# LED_TwoBars.net
KiCad netlist of a schematic drawn in Altium Designer
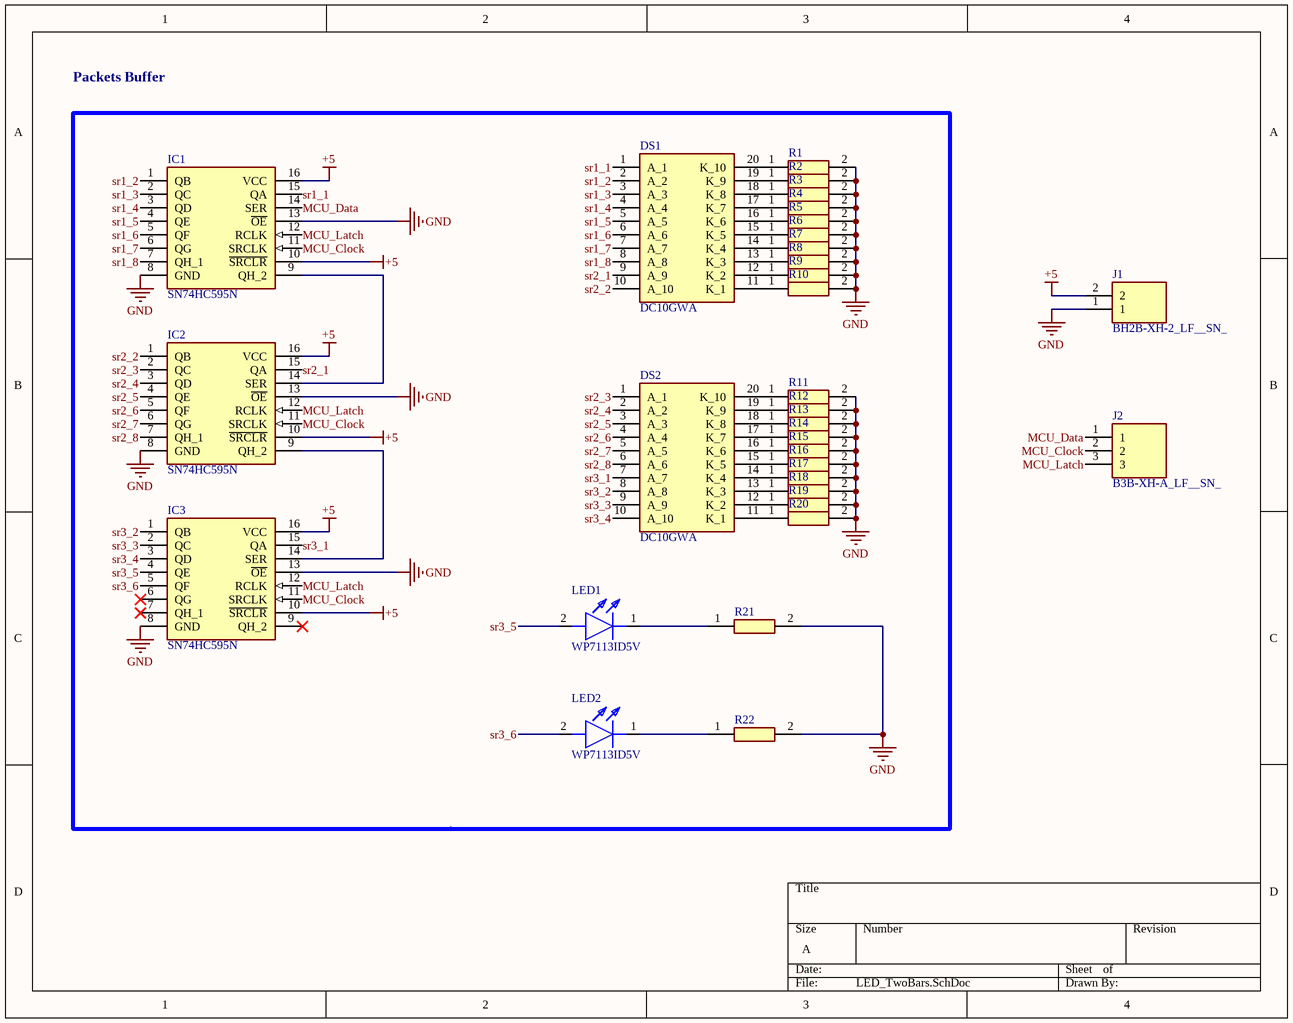
[diagram p0: LED_TwoBars.SchDoc]

(export (version "E")
  (design (tool "Eeschema 10.0.6"))
  (components
    (comp (ref "DS1")
      (value "DC10GWA")
      (footprint "LED_Buffer:DIPS750W75P254L2540H825Q20N")
      (description "Display")
      (fields (field (name "MOUSER PART NUMBER") "604-DC10GWA"))
      (libsource (lib "*") (part "DC10GWA"))
    )
    (comp (ref "DS2")
      (value "DC10GWA")
      (footprint "LED_Buffer:DIPS750W75P254L2540H825Q20N")
      (description "Display")
      (fields (field (name "MOUSER PART NUMBER") "604-DC10GWA"))
      (libsource (lib "*") (part "DC10GWA"))
    )
    (comp (ref "IC1")
      (value "SN74HC595N")
      (footprint "LED_Buffer:DIP794W53P254L1930H508Q16N")
      (description "Integrated Circuit")
      (fields (field (name "MOUSER PART NUMBER") "595-SN74HC595N"))
      (libsource (lib "*") (part "SN74HC595N"))
    )
    (comp (ref "IC2")
      (value "SN74HC595N")
      (footprint "LED_Buffer:DIP794W53P254L1930H508Q16N")
      (description "Integrated Circuit")
      (fields (field (name "MOUSER PART NUMBER") "595-SN74HC595N"))
      (libsource (lib "*") (part "SN74HC595N"))
    )
    (comp (ref "IC3")
      (value "SN74HC595N")
      (footprint "LED_Buffer:DIP794W53P254L1930H508Q16N")
      (description "Integrated Circuit")
      (fields (field (name "MOUSER PART NUMBER") "595-SN74HC595N"))
      (libsource (lib "*") (part "SN74HC595N"))
    )
    (comp (ref "J1")
      (value "BH2B-XH-2_LF__SN_")
      (footprint "LED_Buffer:BH2BXH2LFSN")
      (description "Connector")
      (fields (field (name "MANUFACTURER_PART_NUMBER") "BH2B-XH-2(LF)(SN)"))
      (libsource (lib "LED_Buffer") (part "BH2B-XH-2_LF__SN_"))
    )
    (comp (ref "J2")
      (value "B3B-XH-A_LF__SN_")
      (footprint "LED_Buffer:B3BXHALFSN")
      (description "Connector")
      (fields
        (field (name "MANUFACTURER_PART_NUMBER") "B3B-XH-A(LF)(SN)")
        (field (name "MOUSER PART NUMBER") "306-B3BXHALFSNP")
      )
      (libsource (lib "*") (part "B3B-XH-A_LF__SN_"))
    )
    (comp (ref "LED1")
      (value "WP7113ID5V")
      (footprint "LED_TwoBars:WP7113ID5V")
      (description "LED")
      (fields (field (name "MOUSER PART NUMBER") "604-WP7113ID5V"))
      (libsource (lib "*") (part "WP7113ID5V"))
    )
    (comp (ref "LED2")
      (value "WP7113ID5V")
      (footprint "LED_TwoBars:WP7113ID5V")
      (description "LED")
      (fields (field (name "MOUSER PART NUMBER") "604-WP7113ID5V"))
      (libsource (lib "*") (part "WP7113ID5V"))
    )
    (comp (ref "R1")
      (value "330")
      (footprint "LED_Buffer:RESC3126X65N")
      (description "Resistor")
      (fields (field (name "MANUFACTURER_PART_NUMBER") "RC1210FR-07330RL"))
      (libsource (lib "*") (part "RC1210FR-07330RL"))
    )
    (comp (ref "R2")
      (value "RC1210FR-07330RL")
      (footprint "LED_Buffer:RESC3126X65N")
      (description "Resistor")
      (libsource (lib "*") (part "RC1210FR-07330RL"))
    )
    (comp (ref "R3")
      (value "330")
      (footprint "LED_Buffer:RESC3126X65N")
      (description "Resistor")
      (fields (field (name "MANUFACTURER_PART_NUMBER") "RC1210FR-07330RL"))
      (libsource (lib "*") (part "RC1210FR-07330RL"))
    )
    (comp (ref "R4")
      (value "RC1210FR-07330RL")
      (footprint "LED_Buffer:RESC3126X65N")
      (description "Resistor")
      (libsource (lib "*") (part "RC1210FR-07330RL"))
    )
    (comp (ref "R5")
      (value "330")
      (footprint "LED_Buffer:RESC3126X65N")
      (description "Resistor")
      (fields (field (name "MANUFACTURER_PART_NUMBER") "RC1210FR-07330RL"))
      (libsource (lib "*") (part "RC1210FR-07330RL"))
    )
    (comp (ref "R6")
      (value "RC1210FR-07330RL")
      (footprint "LED_Buffer:RESC3126X65N")
      (description "Resistor")
      (libsource (lib "*") (part "RC1210FR-07330RL"))
    )
    (comp (ref "R7")
      (value "330")
      (footprint "LED_Buffer:RESC3126X65N")
      (description "Resistor")
      (fields (field (name "MANUFACTURER_PART_NUMBER") "RC1210FR-07330RL"))
      (libsource (lib "*") (part "RC1210FR-07330RL"))
    )
    (comp (ref "R8")
      (value "RC1210FR-07330RL")
      (footprint "LED_Buffer:RESC3126X65N")
      (description "Resistor")
      (libsource (lib "*") (part "RC1210FR-07330RL"))
    )
    (comp (ref "R9")
      (value "330")
      (footprint "LED_Buffer:RESC3126X65N")
      (description "Resistor")
      (fields (field (name "MANUFACTURER_PART_NUMBER") "RC1210FR-07330RL"))
      (libsource (lib "*") (part "RC1210FR-07330RL"))
    )
    (comp (ref "R10")
      (value "330")
      (footprint "LED_Buffer:RESC3126X65N")
      (description "Resistor")
      (fields (field (name "MANUFACTURER_PART_NUMBER") "RC1210FR-07330RL"))
      (libsource (lib "*") (part "RC1210FR-07330RL"))
    )
    (comp (ref "R11")
      (value "330")
      (footprint "LED_Buffer:RESC3126X65N")
      (description "Resistor")
      (fields (field (name "MANUFACTURER_PART_NUMBER") "RC1210FR-07330RL"))
      (libsource (lib "*") (part "RC1210FR-07330RL"))
    )
    (comp (ref "R12")
      (value "330")
      (footprint "LED_Buffer:RESC3126X65N")
      (description "Resistor")
      (fields (field (name "MANUFACTURER_PART_NUMBER") "RC1210FR-07330RL"))
      (libsource (lib "*") (part "RC1210FR-07330RL"))
    )
    (comp (ref "R13")
      (value "330")
      (footprint "LED_Buffer:RESC3126X65N")
      (description "Resistor")
      (fields (field (name "MANUFACTURER_PART_NUMBER") "RC1210FR-07330RL"))
      (libsource (lib "*") (part "RC1210FR-07330RL"))
    )
    (comp (ref "R14")
      (value "330")
      (footprint "LED_Buffer:RESC3126X65N")
      (description "Resistor")
      (fields (field (name "MANUFACTURER_PART_NUMBER") "RC1210FR-07330RL"))
      (libsource (lib "*") (part "RC1210FR-07330RL"))
    )
    (comp (ref "R15")
      (value "330")
      (footprint "LED_Buffer:RESC3126X65N")
      (description "Resistor")
      (fields (field (name "MANUFACTURER_PART_NUMBER") "RC1210FR-07330RL"))
      (libsource (lib "*") (part "RC1210FR-07330RL"))
    )
    (comp (ref "R16")
      (value "330")
      (footprint "LED_Buffer:RESC3126X65N")
      (description "Resistor")
      (fields (field (name "MANUFACTURER_PART_NUMBER") "RC1210FR-07330RL"))
      (libsource (lib "*") (part "RC1210FR-07330RL"))
    )
    (comp (ref "R17")
      (value "330")
      (footprint "LED_Buffer:RESC3126X65N")
      (description "Resistor")
      (fields (field (name "MANUFACTURER_PART_NUMBER") "RC1210FR-07330RL"))
      (libsource (lib "*") (part "RC1210FR-07330RL"))
    )
    (comp (ref "R18")
      (value "330")
      (footprint "LED_Buffer:RESC3126X65N")
      (description "Resistor")
      (fields (field (name "MANUFACTURER_PART_NUMBER") "RC1210FR-07330RL"))
      (libsource (lib "*") (part "RC1210FR-07330RL"))
    )
    (comp (ref "R19")
      (value "RC1210FR-07330RL")
      (footprint "LED_Buffer:RESC3126X65N")
      (description "Resistor")
      (libsource (lib "*") (part "RC1210FR-07330RL"))
    )
    (comp (ref "R20")
      (value "330")
      (footprint "LED_Buffer:RESC3126X65N")
      (description "Resistor")
      (fields (field (name "MANUFACTURER_PART_NUMBER") "RC1210FR-07330RL"))
      (libsource (lib "*") (part "RC1210FR-07330RL"))
    )
    (comp (ref "R21")
      (value "330")
      (footprint "LED_Buffer:RESC3126X65N")
      (description "Resistor")
      (fields (field (name "MANUFACTURER_PART_NUMBER") "RC1210FR-07330RL"))
      (libsource (lib "*") (part "RC1210FR-07330RL"))
    )
    (comp (ref "R22")
      (value "330")
      (footprint "LED_Buffer:RESC3126X65N")
      (description "Resistor")
      (fields (field (name "MANUFACTURER_PART_NUMBER") "RC1210FR-07330RL"))
      (libsource (lib "*") (part "RC1210FR-07330RL"))
    )
  )
  (nets
    (net (code "1") (name "+5") (class "Default")
      (node (ref "IC1") (pin "10") (pinfunction "~{SRCLR}_10") (pintype "passive"))
      (node (ref "IC1") (pin "16") (pinfunction "VCC_16") (pintype "power_in"))
      (node (ref "IC2") (pin "10") (pinfunction "~{SRCLR}_10") (pintype "passive"))
      (node (ref "IC2") (pin "16") (pinfunction "VCC_16") (pintype "power_in"))
      (node (ref "IC3") (pin "10") (pinfunction "~{SRCLR}_10") (pintype "passive"))
      (node (ref "IC3") (pin "16") (pinfunction "VCC_16") (pintype "power_in"))
      (node (ref "J1") (pin "2") (pinfunction "2_2") (pintype "passive"))
    )
    (net (code "2") (name "/MCU_Clock") (class "Default")
      (node (ref "IC1") (pin "11") (pinfunction "SRCLK_11") (pintype "input"))
      (node (ref "IC2") (pin "11") (pinfunction "SRCLK_11") (pintype "input"))
      (node (ref "IC3") (pin "11") (pinfunction "SRCLK_11") (pintype "input"))
      (node (ref "J2") (pin "2") (pinfunction "2_2") (pintype "passive"))
    )
    (net (code "3") (name "/MCU_Data") (class "Default")
      (node (ref "IC1") (pin "14") (pinfunction "SER_14") (pintype "passive"))
      (node (ref "J2") (pin "1") (pinfunction "1_1") (pintype "passive"))
    )
    (net (code "4") (name "/MCU_Latch") (class "Default")
      (node (ref "IC1") (pin "12") (pinfunction "RCLK_12") (pintype "input"))
      (node (ref "IC2") (pin "12") (pinfunction "RCLK_12") (pintype "input"))
      (node (ref "IC3") (pin "12") (pinfunction "RCLK_12") (pintype "input"))
      (node (ref "J2") (pin "3") (pinfunction "3_3") (pintype "passive"))
    )
    (net (code "5") (name "/sr1_1") (class "Default")
      (node (ref "DS1") (pin "1") (pinfunction "A_1_1") (pintype "passive"))
      (node (ref "IC1") (pin "15") (pinfunction "QA_15") (pintype "passive"))
    )
    (net (code "6") (name "/sr1_2") (class "Default")
      (node (ref "DS1") (pin "2") (pinfunction "A_2_2") (pintype "passive"))
      (node (ref "IC1") (pin "1") (pinfunction "QB_1") (pintype "passive"))
    )
    (net (code "7") (name "/sr1_3") (class "Default")
      (node (ref "DS1") (pin "3") (pinfunction "A_3_3") (pintype "passive"))
      (node (ref "IC1") (pin "2") (pinfunction "QC_2") (pintype "passive"))
    )
    (net (code "8") (name "/sr1_4") (class "Default")
      (node (ref "DS1") (pin "4") (pinfunction "A_4_4") (pintype "passive"))
      (node (ref "IC1") (pin "3") (pinfunction "QD_3") (pintype "passive"))
    )
    (net (code "9") (name "/sr1_5") (class "Default")
      (node (ref "DS1") (pin "5") (pinfunction "A_5_5") (pintype "passive"))
      (node (ref "IC1") (pin "4") (pinfunction "QE_4") (pintype "passive"))
    )
    (net (code "10") (name "/sr1_6") (class "Default")
      (node (ref "DS1") (pin "6") (pinfunction "A_6_6") (pintype "passive"))
      (node (ref "IC1") (pin "5") (pinfunction "QF_5") (pintype "passive"))
    )
    (net (code "11") (name "/sr1_7") (class "Default")
      (node (ref "DS1") (pin "7") (pinfunction "A_7_7") (pintype "passive"))
      (node (ref "IC1") (pin "6") (pinfunction "QG_6") (pintype "passive"))
    )
    (net (code "12") (name "/sr1_8") (class "Default")
      (node (ref "DS1") (pin "8") (pinfunction "A_8_8") (pintype "passive"))
      (node (ref "IC1") (pin "7") (pinfunction "QH_1_7") (pintype "passive"))
    )
    (net (code "13") (name "/sr2_1") (class "Default")
      (node (ref "DS1") (pin "9") (pinfunction "A_9_9") (pintype "passive"))
      (node (ref "IC2") (pin "15") (pinfunction "QA_15") (pintype "passive"))
    )
    (net (code "14") (name "/sr2_2") (class "Default")
      (node (ref "DS1") (pin "10") (pinfunction "A_10_10") (pintype "passive"))
      (node (ref "IC2") (pin "1") (pinfunction "QB_1") (pintype "passive"))
    )
    (net (code "15") (name "/sr2_3") (class "Default")
      (node (ref "DS2") (pin "1") (pinfunction "A_1_1") (pintype "passive"))
      (node (ref "IC2") (pin "2") (pinfunction "QC_2") (pintype "passive"))
    )
    (net (code "16") (name "/sr2_4") (class "Default")
      (node (ref "DS2") (pin "2") (pinfunction "A_2_2") (pintype "passive"))
      (node (ref "IC2") (pin "3") (pinfunction "QD_3") (pintype "passive"))
    )
    (net (code "17") (name "/sr2_5") (class "Default")
      (node (ref "DS2") (pin "3") (pinfunction "A_3_3") (pintype "passive"))
      (node (ref "IC2") (pin "4") (pinfunction "QE_4") (pintype "passive"))
    )
    (net (code "18") (name "/sr2_6") (class "Default")
      (node (ref "DS2") (pin "4") (pinfunction "A_4_4") (pintype "passive"))
      (node (ref "IC2") (pin "5") (pinfunction "QF_5") (pintype "passive"))
    )
    (net (code "19") (name "/sr2_7") (class "Default")
      (node (ref "DS2") (pin "5") (pinfunction "A_5_5") (pintype "passive"))
      (node (ref "IC2") (pin "6") (pinfunction "QG_6") (pintype "passive"))
    )
    (net (code "20") (name "/sr2_8") (class "Default")
      (node (ref "DS2") (pin "6") (pinfunction "A_6_6") (pintype "passive"))
      (node (ref "IC2") (pin "7") (pinfunction "QH_1_7") (pintype "passive"))
    )
    (net (code "21") (name "/sr3_1") (class "Default")
      (node (ref "DS2") (pin "7") (pinfunction "A_7_7") (pintype "passive"))
      (node (ref "IC3") (pin "15") (pinfunction "QA_15") (pintype "passive"))
    )
    (net (code "22") (name "/sr3_2") (class "Default")
      (node (ref "DS2") (pin "8") (pinfunction "A_8_8") (pintype "passive"))
      (node (ref "IC3") (pin "1") (pinfunction "QB_1") (pintype "passive"))
    )
    (net (code "23") (name "/sr3_3") (class "Default")
      (node (ref "DS2") (pin "9") (pinfunction "A_9_9") (pintype "passive"))
      (node (ref "IC3") (pin "2") (pinfunction "QC_2") (pintype "passive"))
    )
    (net (code "24") (name "/sr3_4") (class "Default")
      (node (ref "DS2") (pin "10") (pinfunction "A_10_10") (pintype "passive"))
      (node (ref "IC3") (pin "3") (pinfunction "QD_3") (pintype "passive"))
    )
    (net (code "25") (name "/sr3_5") (class "Default")
      (node (ref "IC3") (pin "4") (pinfunction "QE_4") (pintype "passive"))
      (node (ref "LED1") (pin "2") (pinfunction "A_2") (pintype "passive"))
    )
    (net (code "26") (name "/sr3_6") (class "Default")
      (node (ref "IC3") (pin "5") (pinfunction "QF_5") (pintype "passive"))
      (node (ref "LED2") (pin "2") (pinfunction "A_2") (pintype "passive"))
    )
    (net (code "27") (name "GND") (class "Default")
      (node (ref "IC1") (pin "13") (pinfunction "~{OE}_13") (pintype "passive"))
      (node (ref "IC1") (pin "8") (pinfunction "GND_8") (pintype "power_in"))
      (node (ref "IC2") (pin "13") (pinfunction "~{OE}_13") (pintype "passive"))
      (node (ref "IC2") (pin "8") (pinfunction "GND_8") (pintype "power_in"))
      (node (ref "IC3") (pin "13") (pinfunction "~{OE}_13") (pintype "passive"))
      (node (ref "IC3") (pin "8") (pinfunction "GND_8") (pintype "power_in"))
      (node (ref "J1") (pin "1") (pinfunction "1_1") (pintype "passive"))
      (node (ref "R1") (pin "2") (pinfunction "2_2") (pintype "passive"))
      (node (ref "R10") (pin "2") (pinfunction "2_2") (pintype "passive"))
      (node (ref "R11") (pin "2") (pinfunction "2_2") (pintype "passive"))
      (node (ref "R12") (pin "2") (pinfunction "2_2") (pintype "passive"))
      (node (ref "R13") (pin "2") (pinfunction "2_2") (pintype "passive"))
      (node (ref "R14") (pin "2") (pinfunction "2_2") (pintype "passive"))
      (node (ref "R15") (pin "2") (pinfunction "2_2") (pintype "passive"))
      (node (ref "R16") (pin "2") (pinfunction "2_2") (pintype "passive"))
      (node (ref "R17") (pin "2") (pinfunction "2_2") (pintype "passive"))
      (node (ref "R18") (pin "2") (pinfunction "2_2") (pintype "passive"))
      (node (ref "R19") (pin "2") (pinfunction "2_2") (pintype "passive"))
      (node (ref "R2") (pin "2") (pinfunction "2_2") (pintype "passive"))
      (node (ref "R20") (pin "2") (pinfunction "2_2") (pintype "passive"))
      (node (ref "R21") (pin "2") (pinfunction "2_2") (pintype "passive"))
      (node (ref "R22") (pin "2") (pinfunction "2_2") (pintype "passive"))
      (node (ref "R3") (pin "2") (pinfunction "2_2") (pintype "passive"))
      (node (ref "R4") (pin "2") (pinfunction "2_2") (pintype "passive"))
      (node (ref "R5") (pin "2") (pinfunction "2_2") (pintype "passive"))
      (node (ref "R6") (pin "2") (pinfunction "2_2") (pintype "passive"))
      (node (ref "R7") (pin "2") (pinfunction "2_2") (pintype "passive"))
      (node (ref "R8") (pin "2") (pinfunction "2_2") (pintype "passive"))
      (node (ref "R9") (pin "2") (pinfunction "2_2") (pintype "passive"))
    )
    (net (code "28") (name "Net-(DS1-K_1)") (class "Default")
      (node (ref "DS1") (pin "11") (pinfunction "K_1_11") (pintype "passive"))
      (node (ref "R10") (pin "1") (pinfunction "1_1") (pintype "passive"))
    )
    (net (code "29") (name "Net-(DS1-K_2)") (class "Default")
      (node (ref "DS1") (pin "12") (pinfunction "K_2_12") (pintype "passive"))
      (node (ref "R9") (pin "1") (pinfunction "1_1") (pintype "passive"))
    )
    (net (code "30") (name "Net-(DS1-K_3)") (class "Default")
      (node (ref "DS1") (pin "13") (pinfunction "K_3_13") (pintype "passive"))
      (node (ref "R8") (pin "1") (pinfunction "1_1") (pintype "passive"))
    )
    (net (code "31") (name "Net-(DS1-K_4)") (class "Default")
      (node (ref "DS1") (pin "14") (pinfunction "K_4_14") (pintype "passive"))
      (node (ref "R7") (pin "1") (pinfunction "1_1") (pintype "passive"))
    )
    (net (code "32") (name "Net-(DS1-K_5)") (class "Default")
      (node (ref "DS1") (pin "15") (pinfunction "K_5_15") (pintype "passive"))
      (node (ref "R6") (pin "1") (pinfunction "1_1") (pintype "passive"))
    )
    (net (code "33") (name "Net-(DS1-K_6)") (class "Default")
      (node (ref "DS1") (pin "16") (pinfunction "K_6_16") (pintype "passive"))
      (node (ref "R5") (pin "1") (pinfunction "1_1") (pintype "passive"))
    )
    (net (code "34") (name "Net-(DS1-K_7)") (class "Default")
      (node (ref "DS1") (pin "17") (pinfunction "K_7_17") (pintype "passive"))
      (node (ref "R4") (pin "1") (pinfunction "1_1") (pintype "passive"))
    )
    (net (code "35") (name "Net-(DS1-K_8)") (class "Default")
      (node (ref "DS1") (pin "18") (pinfunction "K_8_18") (pintype "passive"))
      (node (ref "R3") (pin "1") (pinfunction "1_1") (pintype "passive"))
    )
    (net (code "36") (name "Net-(DS1-K_9)") (class "Default")
      (node (ref "DS1") (pin "19") (pinfunction "K_9_19") (pintype "passive"))
      (node (ref "R2") (pin "1") (pinfunction "1_1") (pintype "passive"))
    )
    (net (code "37") (name "Net-(DS1-K_10)") (class "Default")
      (node (ref "DS1") (pin "20") (pinfunction "K_10_20") (pintype "passive"))
      (node (ref "R1") (pin "1") (pinfunction "1_1") (pintype "passive"))
    )
    (net (code "38") (name "Net-(DS2-K_1)") (class "Default")
      (node (ref "DS2") (pin "11") (pinfunction "K_1_11") (pintype "passive"))
      (node (ref "R20") (pin "1") (pinfunction "1_1") (pintype "passive"))
    )
    (net (code "39") (name "Net-(DS2-K_2)") (class "Default")
      (node (ref "DS2") (pin "12") (pinfunction "K_2_12") (pintype "passive"))
      (node (ref "R19") (pin "1") (pinfunction "1_1") (pintype "passive"))
    )
    (net (code "40") (name "Net-(DS2-K_3)") (class "Default")
      (node (ref "DS2") (pin "13") (pinfunction "K_3_13") (pintype "passive"))
      (node (ref "R18") (pin "1") (pinfunction "1_1") (pintype "passive"))
    )
    (net (code "41") (name "Net-(DS2-K_4)") (class "Default")
      (node (ref "DS2") (pin "14") (pinfunction "K_4_14") (pintype "passive"))
      (node (ref "R17") (pin "1") (pinfunction "1_1") (pintype "passive"))
    )
    (net (code "42") (name "Net-(DS2-K_5)") (class "Default")
      (node (ref "DS2") (pin "15") (pinfunction "K_5_15") (pintype "passive"))
      (node (ref "R16") (pin "1") (pinfunction "1_1") (pintype "passive"))
    )
    (net (code "43") (name "Net-(DS2-K_6)") (class "Default")
      (node (ref "DS2") (pin "16") (pinfunction "K_6_16") (pintype "passive"))
      (node (ref "R15") (pin "1") (pinfunction "1_1") (pintype "passive"))
    )
    (net (code "44") (name "Net-(DS2-K_7)") (class "Default")
      (node (ref "DS2") (pin "17") (pinfunction "K_7_17") (pintype "passive"))
      (node (ref "R14") (pin "1") (pinfunction "1_1") (pintype "passive"))
    )
    (net (code "45") (name "Net-(DS2-K_8)") (class "Default")
      (node (ref "DS2") (pin "18") (pinfunction "K_8_18") (pintype "passive"))
      (node (ref "R13") (pin "1") (pinfunction "1_1") (pintype "passive"))
    )
    (net (code "46") (name "Net-(DS2-K_9)") (class "Default")
      (node (ref "DS2") (pin "19") (pinfunction "K_9_19") (pintype "passive"))
      (node (ref "R12") (pin "1") (pinfunction "1_1") (pintype "passive"))
    )
    (net (code "47") (name "Net-(DS2-K_10)") (class "Default")
      (node (ref "DS2") (pin "20") (pinfunction "K_10_20") (pintype "passive"))
      (node (ref "R11") (pin "1") (pinfunction "1_1") (pintype "passive"))
    )
    (net (code "48") (name "Net-(IC1-QH_2)") (class "Default")
      (node (ref "IC1") (pin "9") (pinfunction "QH_2_9") (pintype "passive"))
      (node (ref "IC2") (pin "14") (pinfunction "SER_14") (pintype "passive"))
    )
    (net (code "49") (name "Net-(IC2-QH_2)") (class "Default")
      (node (ref "IC2") (pin "9") (pinfunction "QH_2_9") (pintype "passive"))
      (node (ref "IC3") (pin "14") (pinfunction "SER_14") (pintype "passive"))
    )
    (net (code "50") (name "Net-(LED1-K)") (class "Default")
      (node (ref "LED1") (pin "1") (pinfunction "K_1") (pintype "passive"))
      (node (ref "R21") (pin "1") (pinfunction "1_1") (pintype "passive"))
    )
    (net (code "51") (name "Net-(LED2-K)") (class "Default")
      (node (ref "LED2") (pin "1") (pinfunction "K_1") (pintype "passive"))
      (node (ref "R22") (pin "1") (pinfunction "1_1") (pintype "passive"))
    )
    (net (code "52") (name "unconnected-(IC3-QG-Pad6)") (class "Default")
      (node (ref "IC3") (pin "6") (pinfunction "QG_6") (pintype "passive+no_connect"))
    )
    (net (code "53") (name "unconnected-(IC3-QH_1-Pad7)") (class "Default")
      (node (ref "IC3") (pin "7") (pinfunction "QH_1_7") (pintype "passive+no_connect"))
    )
    (net (code "54") (name "unconnected-(IC3-QH_2-Pad9)") (class "Default")
      (node (ref "IC3") (pin "9") (pinfunction "QH_2_9") (pintype "passive+no_connect"))
    )
  )
)
